# bottom_3-28-21.net
KiCad netlist of a schematic drawn in EAGLE
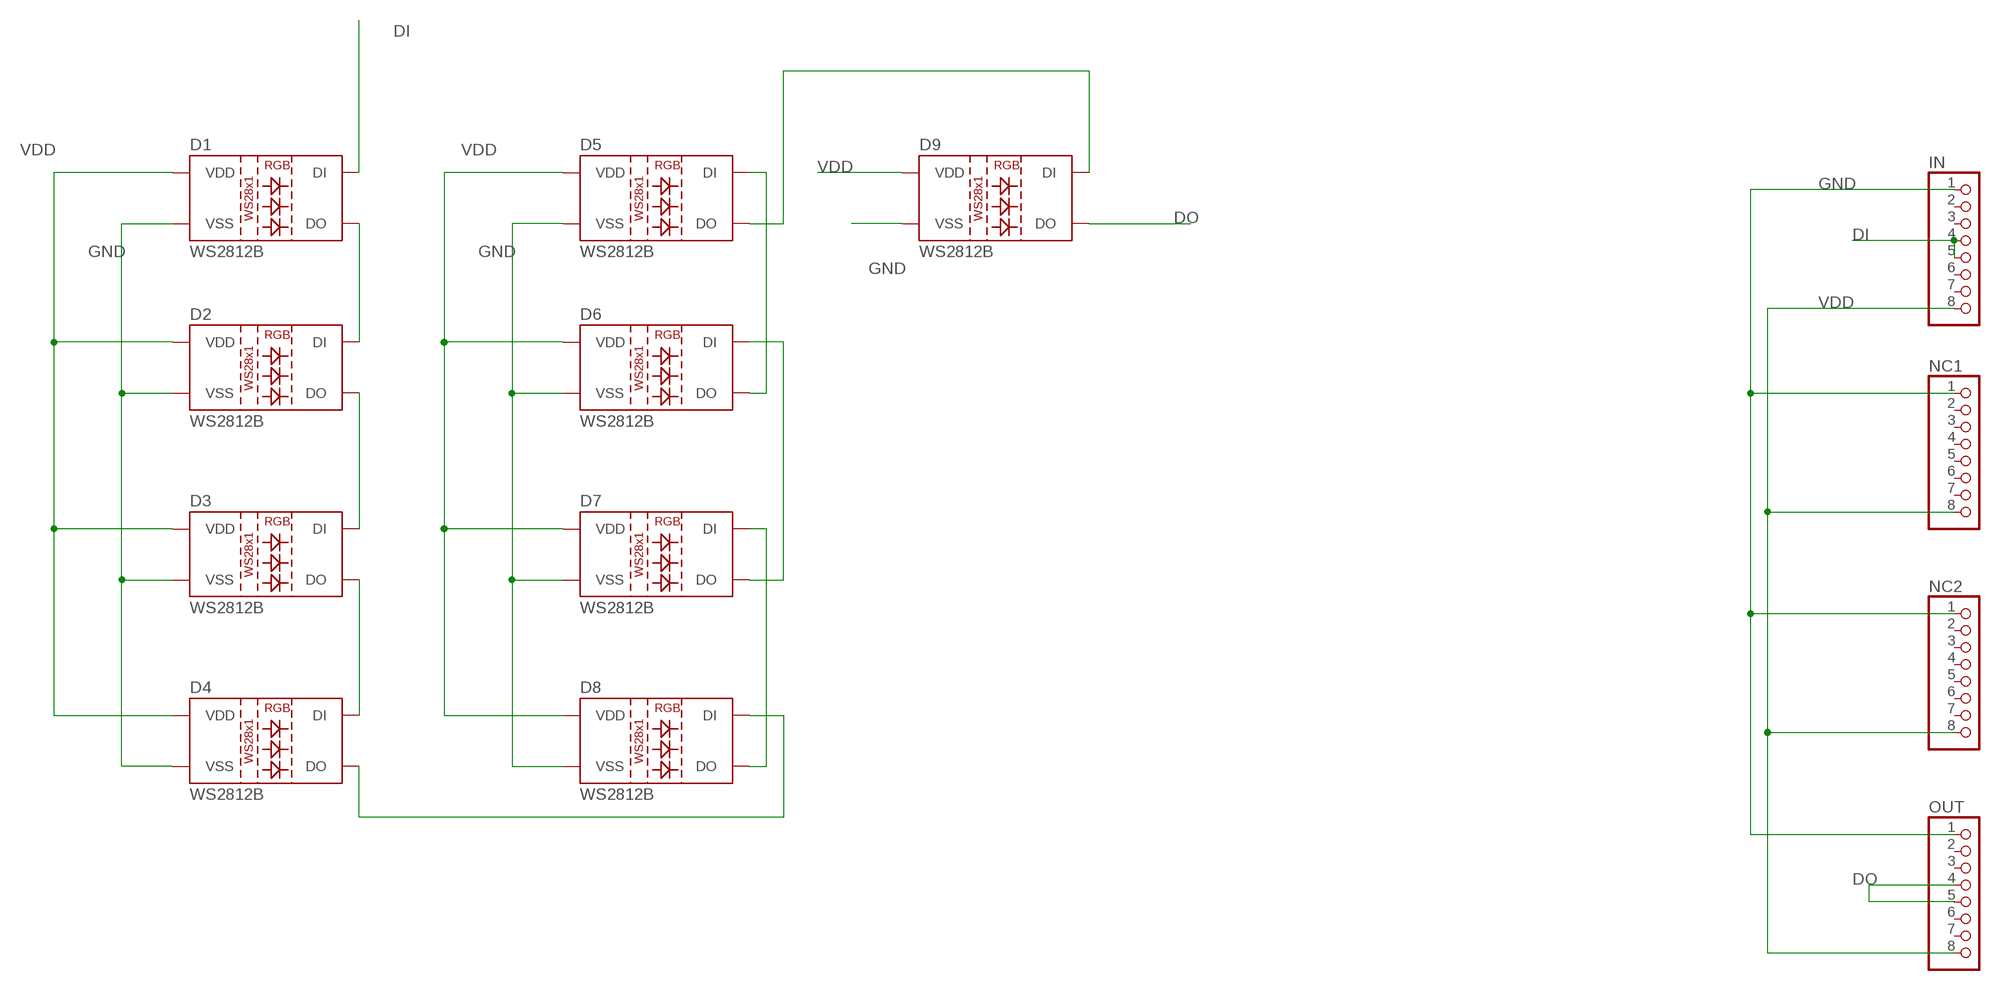
[diagram p0: schematic, sheet 1]

(export (version "E")
  (design (tool "Eeschema 10.0.6"))
  (components
    (comp (ref "D1")
      (value "WS2812B")
      (footprint "eagle-import:WS2812B")
      (libsource (lib "eagle-import") (part "WS2812B"))
    )
    (comp (ref "D2")
      (value "WS2812B")
      (footprint "eagle-import:WS2812B")
      (libsource (lib "eagle-import") (part "WS2812B"))
    )
    (comp (ref "D3")
      (value "WS2812B")
      (footprint "eagle-import:WS2812B")
      (libsource (lib "eagle-import") (part "WS2812B"))
    )
    (comp (ref "D4")
      (value "WS2812B")
      (footprint "eagle-import:WS2812B")
      (libsource (lib "eagle-import") (part "WS2812B"))
    )
    (comp (ref "D5")
      (value "WS2812B")
      (footprint "eagle-import:WS2812B")
      (libsource (lib "eagle-import") (part "WS2812B"))
    )
    (comp (ref "D6")
      (value "WS2812B")
      (footprint "eagle-import:WS2812B")
      (libsource (lib "eagle-import") (part "WS2812B"))
    )
    (comp (ref "D7")
      (value "WS2812B")
      (footprint "eagle-import:WS2812B")
      (libsource (lib "eagle-import") (part "WS2812B"))
    )
    (comp (ref "D8")
      (value "WS2812B")
      (footprint "eagle-import:WS2812B")
      (libsource (lib "eagle-import") (part "WS2812B"))
    )
    (comp (ref "D9")
      (value "WS2812B")
      (footprint "eagle-import:WS2812B")
      (libsource (lib "eagle-import") (part "WS2812B"))
    )
    (comp (ref "IN")
      (value "PINHD-1X8")
      (footprint "eagle-import:1X08")
      (libsource (lib "eagle-import") (part "PINHD-1X8"))
    )
    (comp (ref "NC1")
      (value "PINHD-1X8")
      (footprint "eagle-import:1X08")
      (libsource (lib "eagle-import") (part "PINHD-1X8"))
    )
    (comp (ref "NC2")
      (value "PINHD-1X8")
      (footprint "eagle-import:1X08")
      (libsource (lib "eagle-import") (part "PINHD-1X8"))
    )
    (comp (ref "OUT")
      (value "PINHD-1X8")
      (footprint "eagle-import:1X08")
      (libsource (lib "eagle-import") (part "PINHD-1X8"))
    )
  )
  (nets
    (net (code "1") (name "/DI") (class "Default")
      (node (ref "D1") (pin "4") (pinfunction "DI_4") (pintype "bidirectional"))
      (node (ref "IN") (pin "4") (pinfunction "4_4") (pintype "passive"))
      (node (ref "IN") (pin "5") (pinfunction "5_5") (pintype "passive"))
    )
    (net (code "2") (name "/DO") (class "Default")
      (node (ref "D9") (pin "2") (pinfunction "DO_2") (pintype "bidirectional"))
      (node (ref "OUT") (pin "4") (pinfunction "4_4") (pintype "passive"))
      (node (ref "OUT") (pin "5") (pinfunction "5_5") (pintype "passive"))
    )
    (net (code "3") (name "/GND") (class "Default")
      (node (ref "D1") (pin "3") (pinfunction "VSS_3") (pintype "bidirectional"))
      (node (ref "D2") (pin "3") (pinfunction "VSS_3") (pintype "bidirectional"))
      (node (ref "D3") (pin "3") (pinfunction "VSS_3") (pintype "bidirectional"))
      (node (ref "D4") (pin "3") (pinfunction "VSS_3") (pintype "bidirectional"))
      (node (ref "D5") (pin "3") (pinfunction "VSS_3") (pintype "bidirectional"))
      (node (ref "D6") (pin "3") (pinfunction "VSS_3") (pintype "bidirectional"))
      (node (ref "D7") (pin "3") (pinfunction "VSS_3") (pintype "bidirectional"))
      (node (ref "D8") (pin "3") (pinfunction "VSS_3") (pintype "bidirectional"))
      (node (ref "D9") (pin "3") (pinfunction "VSS_3") (pintype "bidirectional"))
      (node (ref "IN") (pin "1") (pinfunction "1_1") (pintype "passive"))
      (node (ref "NC1") (pin "1") (pinfunction "1_1") (pintype "passive"))
      (node (ref "NC2") (pin "1") (pinfunction "1_1") (pintype "passive"))
      (node (ref "OUT") (pin "1") (pinfunction "1_1") (pintype "passive"))
    )
    (net (code "4") (name "/VDD") (class "Default")
      (node (ref "D1") (pin "1") (pinfunction "VDD_1") (pintype "bidirectional"))
      (node (ref "D2") (pin "1") (pinfunction "VDD_1") (pintype "bidirectional"))
      (node (ref "D3") (pin "1") (pinfunction "VDD_1") (pintype "bidirectional"))
      (node (ref "D4") (pin "1") (pinfunction "VDD_1") (pintype "bidirectional"))
      (node (ref "D5") (pin "1") (pinfunction "VDD_1") (pintype "bidirectional"))
      (node (ref "D6") (pin "1") (pinfunction "VDD_1") (pintype "bidirectional"))
      (node (ref "D7") (pin "1") (pinfunction "VDD_1") (pintype "bidirectional"))
      (node (ref "D8") (pin "1") (pinfunction "VDD_1") (pintype "bidirectional"))
      (node (ref "D9") (pin "1") (pinfunction "VDD_1") (pintype "bidirectional"))
      (node (ref "IN") (pin "8") (pinfunction "8_8") (pintype "passive"))
      (node (ref "NC1") (pin "8") (pinfunction "8_8") (pintype "passive"))
      (node (ref "NC2") (pin "8") (pinfunction "8_8") (pintype "passive"))
      (node (ref "OUT") (pin "8") (pinfunction "8_8") (pintype "passive"))
    )
    (net (code "5") (name "Net-(D1-DO)") (class "Default")
      (node (ref "D1") (pin "2") (pinfunction "DO_2") (pintype "bidirectional"))
      (node (ref "D2") (pin "4") (pinfunction "DI_4") (pintype "bidirectional"))
    )
    (net (code "6") (name "Net-(D2-DO)") (class "Default")
      (node (ref "D2") (pin "2") (pinfunction "DO_2") (pintype "bidirectional"))
      (node (ref "D3") (pin "4") (pinfunction "DI_4") (pintype "bidirectional"))
    )
    (net (code "7") (name "Net-(D3-DO)") (class "Default")
      (node (ref "D3") (pin "2") (pinfunction "DO_2") (pintype "bidirectional"))
      (node (ref "D4") (pin "4") (pinfunction "DI_4") (pintype "bidirectional"))
    )
    (net (code "8") (name "Net-(D4-DO)") (class "Default")
      (node (ref "D4") (pin "2") (pinfunction "DO_2") (pintype "bidirectional"))
      (node (ref "D8") (pin "4") (pinfunction "DI_4") (pintype "bidirectional"))
    )
    (net (code "9") (name "Net-(D5-DI)") (class "Default")
      (node (ref "D5") (pin "4") (pinfunction "DI_4") (pintype "bidirectional"))
      (node (ref "D6") (pin "2") (pinfunction "DO_2") (pintype "bidirectional"))
    )
    (net (code "10") (name "Net-(D5-DO)") (class "Default")
      (node (ref "D5") (pin "2") (pinfunction "DO_2") (pintype "bidirectional"))
      (node (ref "D9") (pin "4") (pinfunction "DI_4") (pintype "bidirectional"))
    )
    (net (code "11") (name "Net-(D6-DI)") (class "Default")
      (node (ref "D6") (pin "4") (pinfunction "DI_4") (pintype "bidirectional"))
      (node (ref "D7") (pin "2") (pinfunction "DO_2") (pintype "bidirectional"))
    )
    (net (code "12") (name "Net-(D7-DI)") (class "Default")
      (node (ref "D7") (pin "4") (pinfunction "DI_4") (pintype "bidirectional"))
      (node (ref "D8") (pin "2") (pinfunction "DO_2") (pintype "bidirectional"))
    )
    (net (code "13") (name "unconnected-(IN-Pad2)") (class "Default")
      (node (ref "IN") (pin "2") (pinfunction "2_2") (pintype "passive"))
    )
    (net (code "14") (name "unconnected-(IN-Pad3)") (class "Default")
      (node (ref "IN") (pin "3") (pinfunction "3_3") (pintype "passive"))
    )
    (net (code "15") (name "unconnected-(IN-Pad6)") (class "Default")
      (node (ref "IN") (pin "6") (pinfunction "6_6") (pintype "passive"))
    )
    (net (code "16") (name "unconnected-(IN-Pad7)") (class "Default")
      (node (ref "IN") (pin "7") (pinfunction "7_7") (pintype "passive"))
    )
    (net (code "17") (name "unconnected-(NC1-Pad2)") (class "Default")
      (node (ref "NC1") (pin "2") (pinfunction "2_2") (pintype "passive"))
    )
    (net (code "18") (name "unconnected-(NC1-Pad3)") (class "Default")
      (node (ref "NC1") (pin "3") (pinfunction "3_3") (pintype "passive"))
    )
    (net (code "19") (name "unconnected-(NC1-Pad4)") (class "Default")
      (node (ref "NC1") (pin "4") (pinfunction "4_4") (pintype "passive"))
    )
    (net (code "20") (name "unconnected-(NC1-Pad5)") (class "Default")
      (node (ref "NC1") (pin "5") (pinfunction "5_5") (pintype "passive"))
    )
    (net (code "21") (name "unconnected-(NC1-Pad6)") (class "Default")
      (node (ref "NC1") (pin "6") (pinfunction "6_6") (pintype "passive"))
    )
    (net (code "22") (name "unconnected-(NC1-Pad7)") (class "Default")
      (node (ref "NC1") (pin "7") (pinfunction "7_7") (pintype "passive"))
    )
    (net (code "23") (name "unconnected-(NC2-Pad2)") (class "Default")
      (node (ref "NC2") (pin "2") (pinfunction "2_2") (pintype "passive"))
    )
    (net (code "24") (name "unconnected-(NC2-Pad3)") (class "Default")
      (node (ref "NC2") (pin "3") (pinfunction "3_3") (pintype "passive"))
    )
    (net (code "25") (name "unconnected-(NC2-Pad4)") (class "Default")
      (node (ref "NC2") (pin "4") (pinfunction "4_4") (pintype "passive"))
    )
    (net (code "26") (name "unconnected-(NC2-Pad5)") (class "Default")
      (node (ref "NC2") (pin "5") (pinfunction "5_5") (pintype "passive"))
    )
    (net (code "27") (name "unconnected-(NC2-Pad6)") (class "Default")
      (node (ref "NC2") (pin "6") (pinfunction "6_6") (pintype "passive"))
    )
    (net (code "28") (name "unconnected-(NC2-Pad7)") (class "Default")
      (node (ref "NC2") (pin "7") (pinfunction "7_7") (pintype "passive"))
    )
    (net (code "29") (name "unconnected-(OUT-Pad2)") (class "Default")
      (node (ref "OUT") (pin "2") (pinfunction "2_2") (pintype "passive"))
    )
    (net (code "30") (name "unconnected-(OUT-Pad3)") (class "Default")
      (node (ref "OUT") (pin "3") (pinfunction "3_3") (pintype "passive"))
    )
    (net (code "31") (name "unconnected-(OUT-Pad6)") (class "Default")
      (node (ref "OUT") (pin "6") (pinfunction "6_6") (pintype "passive"))
    )
    (net (code "32") (name "unconnected-(OUT-Pad7)") (class "Default")
      (node (ref "OUT") (pin "7") (pinfunction "7_7") (pintype "passive"))
    )
  )
)
